# DC25_HHV_RE-P1.net
KiCad netlist of a schematic drawn in EAGLE
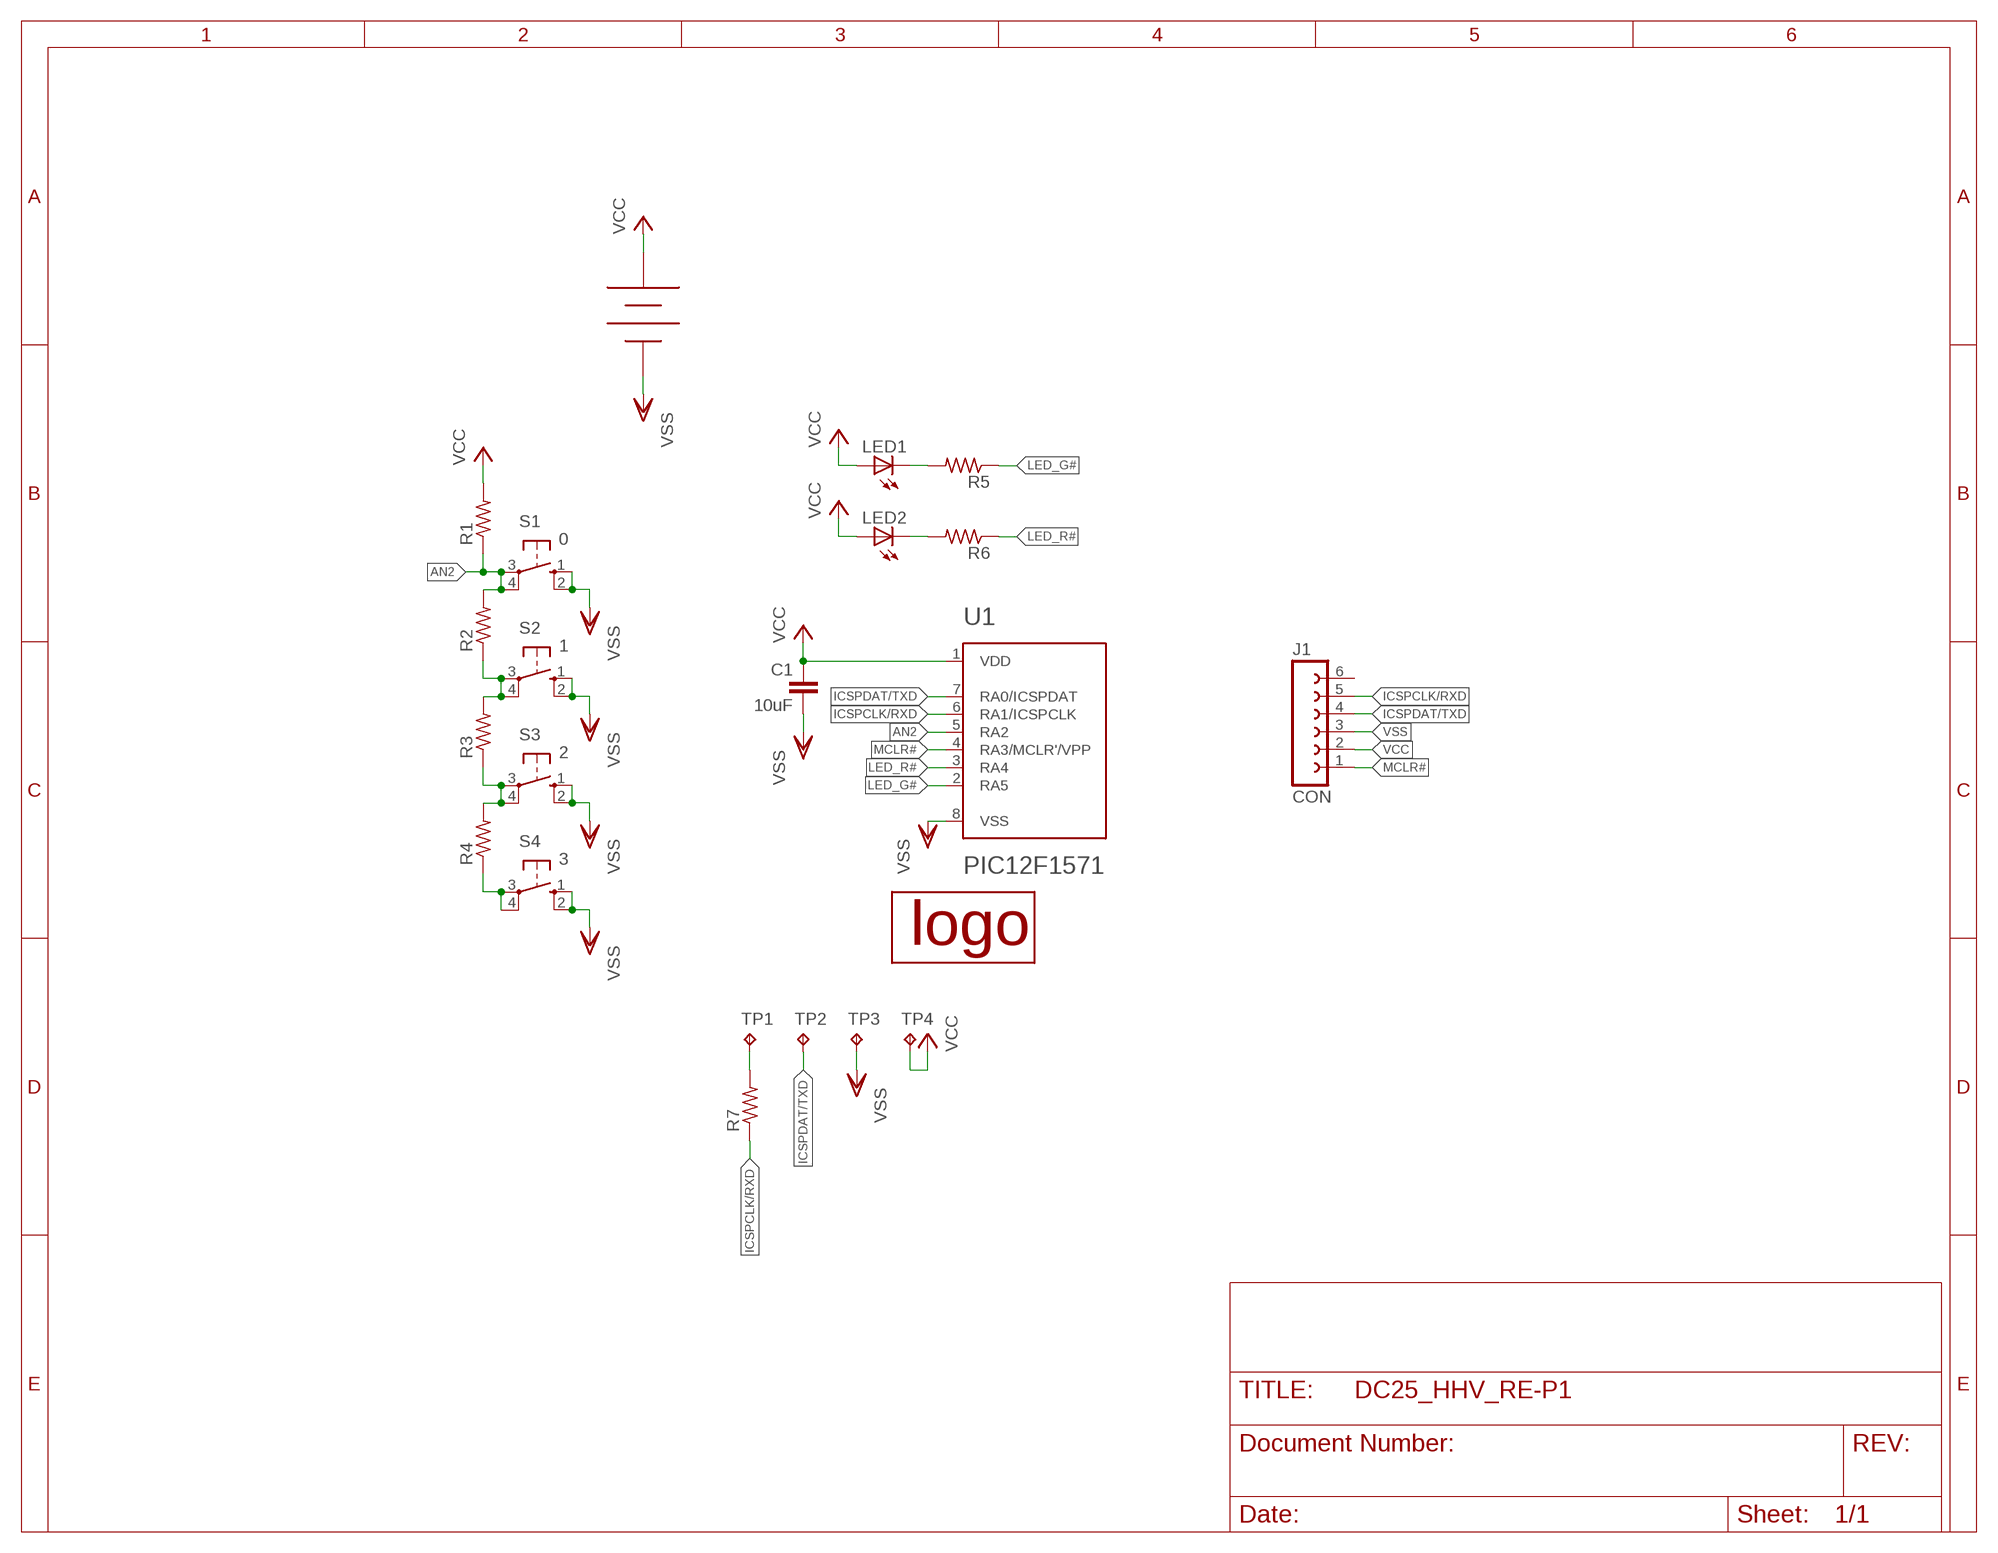
[diagram p0: schematic, sheet 1]

(export (version "E")
  (design (tool "Eeschema 10.0.6"))
  (components
    (comp (ref "BT1")
      (value "BAT-HLD-001-THM")
      (footprint "eagle-import:BAT-HLD-001-THM")
      (libsource (lib "eagle-import") (part "BAT-HLD-001-THM"))
    )
    (comp (ref "C1")
      (value "10uF")
      (footprint "eagle-import:C050-024X044")
      (libsource (lib "eagle-import") (part "C-EU050-024X044"))
    )
    (comp (ref "J1")
      (value "CON")
      (footprint "eagle-import:FE06")
      (libsource (lib "eagle-import") (part "FE06-1"))
    )
    (comp (ref "LED1")
      (value "LED5MM")
      (footprint "eagle-import:LED5MM")
      (libsource (lib "eagle-import") (part "LED5MM"))
    )
    (comp (ref "LED2")
      (value "LED5MM")
      (footprint "eagle-import:LED5MM")
      (libsource (lib "eagle-import") (part "LED5MM"))
    )
    (comp (ref "R1")
      (value "R-US_0207/10")
      (footprint "eagle-import:0207_10")
      (libsource (lib "eagle-import") (part "R-US_0207/10"))
    )
    (comp (ref "R2")
      (value "R-US_0207/10")
      (footprint "eagle-import:0207_10")
      (libsource (lib "eagle-import") (part "R-US_0207/10"))
    )
    (comp (ref "R3")
      (value "R-US_0207/10")
      (footprint "eagle-import:0207_10")
      (libsource (lib "eagle-import") (part "R-US_0207/10"))
    )
    (comp (ref "R4")
      (value "R-US_0207/10")
      (footprint "eagle-import:0207_10")
      (libsource (lib "eagle-import") (part "R-US_0207/10"))
    )
    (comp (ref "R5")
      (value "R-US_0207/10")
      (footprint "eagle-import:0207_10")
      (libsource (lib "eagle-import") (part "R-US_0207/10"))
    )
    (comp (ref "R6")
      (value "R-US_0207/10")
      (footprint "eagle-import:0207_10")
      (libsource (lib "eagle-import") (part "R-US_0207/10"))
    )
    (comp (ref "R7")
      (value "R-US_R0402")
      (footprint "eagle-import:R0402")
      (libsource (lib "eagle-import") (part "R-US_R0402"))
    )
    (comp (ref "S1")
      (value "0")
      (footprint "eagle-import:B3F-10XX")
      (fields (field (name "MPN") "B3F-1000"))
      (libsource (lib "eagle-import") (part "10-XX"))
    )
    (comp (ref "S2")
      (value "1")
      (footprint "eagle-import:B3F-10XX")
      (fields (field (name "MPN") "B3F-1000"))
      (libsource (lib "eagle-import") (part "10-XX"))
    )
    (comp (ref "S3")
      (value "2")
      (footprint "eagle-import:B3F-10XX")
      (fields (field (name "MPN") "B3F-1000"))
      (libsource (lib "eagle-import") (part "10-XX"))
    )
    (comp (ref "S4")
      (value "3")
      (footprint "eagle-import:B3F-10XX")
      (fields (field (name "MPN") "B3F-1000"))
      (libsource (lib "eagle-import") (part "10-XX"))
    )
    (comp (ref "TP1")
      (value "TPTP13R")
      (footprint "eagle-import:TP13R")
      (libsource (lib "eagle-import") (part "TPTP13R"))
    )
    (comp (ref "TP2")
      (value "TPTP13R")
      (footprint "eagle-import:TP13R")
      (libsource (lib "eagle-import") (part "TPTP13R"))
    )
    (comp (ref "TP3")
      (value "TPTP13R")
      (footprint "eagle-import:TP13R")
      (libsource (lib "eagle-import") (part "TPTP13R"))
    )
    (comp (ref "TP4")
      (value "TPTP13R")
      (footprint "eagle-import:TP13R")
      (libsource (lib "eagle-import") (part "TPTP13R"))
    )
    (comp (ref "U$1")
      (value "KBELOGO")
      (footprint "eagle-import:KBELOGO")
      (libsource (lib "eagle-import") (part "KBELOGO"))
    )
    (comp (ref "U1")
      (value "PIC12F1571")
      (footprint "eagle-import:DIL8")
      (libsource (lib "eagle-import") (part "PIC12F1571"))
    )
  )
  (nets
    (net (code "1") (name "AN2") (class "Default")
      (node (ref "R1") (pin "1") (pinfunction "1_1") (pintype "passive"))
      (node (ref "R2") (pin "2") (pinfunction "2_2") (pintype "passive"))
      (node (ref "S1") (pin "3") (pinfunction "P_3") (pintype "passive"))
      (node (ref "S1") (pin "4") (pinfunction "P1_4") (pintype "passive"))
      (node (ref "U1") (pin "5") (pinfunction "RA2_5") (pintype "bidirectional"))
    )
    (net (code "2") (name "ICSPCLK{slash}RXD") (class "Default")
      (node (ref "J1") (pin "5") (pinfunction "5_5") (pintype "passive"))
      (node (ref "R7") (pin "1") (pinfunction "1_1") (pintype "passive"))
      (node (ref "U1") (pin "6") (pinfunction "RA1/ICSPCLK_6") (pintype "bidirectional"))
    )
    (net (code "3") (name "ICSPDAT{slash}TXD") (class "Default")
      (node (ref "J1") (pin "4") (pinfunction "4_4") (pintype "passive"))
      (node (ref "TP2") (pin "TP") (pinfunction "TP_TP") (pintype "input"))
      (node (ref "U1") (pin "7") (pinfunction "RA0/ICSPDAT_7") (pintype "bidirectional"))
    )
    (net (code "4") (name "LED_G#") (class "Default")
      (node (ref "R5") (pin "1") (pinfunction "1_1") (pintype "passive"))
      (node (ref "U1") (pin "2") (pinfunction "RA5_2") (pintype "bidirectional"))
    )
    (net (code "5") (name "LED_R#") (class "Default")
      (node (ref "R6") (pin "1") (pinfunction "1_1") (pintype "passive"))
      (node (ref "U1") (pin "3") (pinfunction "RA4_3") (pintype "bidirectional"))
    )
    (net (code "6") (name "MCLR#") (class "Default")
      (node (ref "J1") (pin "1") (pinfunction "1_1") (pintype "passive"))
      (node (ref "U1") (pin "4") (pinfunction "RA3/MCLR'/VPP_4") (pintype "bidirectional"))
    )
    (net (code "7") (name "Net-(LED1-C)") (class "Default")
      (node (ref "LED1") (pin "K") (pinfunction "C_K") (pintype "passive"))
      (node (ref "R5") (pin "2") (pinfunction "2_2") (pintype "passive"))
    )
    (net (code "8") (name "Net-(LED2-C)") (class "Default")
      (node (ref "LED2") (pin "K") (pinfunction "C_K") (pintype "passive"))
      (node (ref "R6") (pin "2") (pinfunction "2_2") (pintype "passive"))
    )
    (net (code "9") (name "Net-(R7-Pad2)") (class "Default")
      (node (ref "R7") (pin "2") (pinfunction "2_2") (pintype "passive"))
      (node (ref "TP1") (pin "TP") (pinfunction "TP_TP") (pintype "input"))
    )
    (net (code "10") (name "Net-(S2-P)") (class "Default")
      (node (ref "R2") (pin "1") (pinfunction "1_1") (pintype "passive"))
      (node (ref "R3") (pin "2") (pinfunction "2_2") (pintype "passive"))
      (node (ref "S2") (pin "3") (pinfunction "P_3") (pintype "passive"))
      (node (ref "S2") (pin "4") (pinfunction "P1_4") (pintype "passive"))
    )
    (net (code "11") (name "Net-(S3-P)") (class "Default")
      (node (ref "R3") (pin "1") (pinfunction "1_1") (pintype "passive"))
      (node (ref "R4") (pin "2") (pinfunction "2_2") (pintype "passive"))
      (node (ref "S3") (pin "3") (pinfunction "P_3") (pintype "passive"))
      (node (ref "S3") (pin "4") (pinfunction "P1_4") (pintype "passive"))
    )
    (net (code "12") (name "Net-(S4-P)") (class "Default")
      (node (ref "R4") (pin "1") (pinfunction "1_1") (pintype "passive"))
      (node (ref "S4") (pin "3") (pinfunction "P_3") (pintype "passive"))
      (node (ref "S4") (pin "4") (pinfunction "P1_4") (pintype "passive"))
    )
    (net (code "13") (name "VCC") (class "Default")
      (node (ref "BT1") (pin "+@0") (pinfunction "VCC_+@0") (pintype "bidirectional"))
      (node (ref "BT1") (pin "+@1") (pinfunction "VCC_+@1") (pintype "bidirectional"))
      (node (ref "BT1") (pin "+@2") (pinfunction "VCC_+@2") (pintype "bidirectional"))
      (node (ref "BT1") (pin "+@3") (pinfunction "VCC_+@3") (pintype "bidirectional"))
      (node (ref "C1") (pin "1") (pinfunction "1_1") (pintype "passive"))
      (node (ref "J1") (pin "2") (pinfunction "2_2") (pintype "passive"))
      (node (ref "LED1") (pin "A") (pinfunction "A_A") (pintype "passive"))
      (node (ref "LED2") (pin "A") (pinfunction "A_A") (pintype "passive"))
      (node (ref "R1") (pin "2") (pinfunction "2_2") (pintype "passive"))
      (node (ref "TP4") (pin "TP") (pinfunction "TP_TP") (pintype "input"))
      (node (ref "U1") (pin "1") (pinfunction "VDD_1") (pintype "power_in"))
    )
    (net (code "14") (name "VSS") (class "Default")
      (node (ref "BT1") (pin "-") (pinfunction "VSS_-") (pintype "bidirectional"))
      (node (ref "C1") (pin "2") (pinfunction "2_2") (pintype "passive"))
      (node (ref "J1") (pin "3") (pinfunction "3_3") (pintype "passive"))
      (node (ref "S1") (pin "1") (pinfunction "S_1") (pintype "passive"))
      (node (ref "S1") (pin "2") (pinfunction "S1_2") (pintype "passive"))
      (node (ref "S2") (pin "1") (pinfunction "S_1") (pintype "passive"))
      (node (ref "S2") (pin "2") (pinfunction "S1_2") (pintype "passive"))
      (node (ref "S3") (pin "1") (pinfunction "S_1") (pintype "passive"))
      (node (ref "S3") (pin "2") (pinfunction "S1_2") (pintype "passive"))
      (node (ref "S4") (pin "1") (pinfunction "S_1") (pintype "passive"))
      (node (ref "S4") (pin "2") (pinfunction "S1_2") (pintype "passive"))
      (node (ref "TP3") (pin "TP") (pinfunction "TP_TP") (pintype "input"))
      (node (ref "U1") (pin "8") (pinfunction "VSS_8") (pintype "power_in"))
    )
    (net (code "15") (name "unconnected-(J1-Pad6)") (class "Default")
      (node (ref "J1") (pin "6") (pinfunction "6_6") (pintype "passive"))
    )
  )
)
